# Humus_ethernet_dip_v2.net
KiCad netlist of a schematic drawn in EAGLE
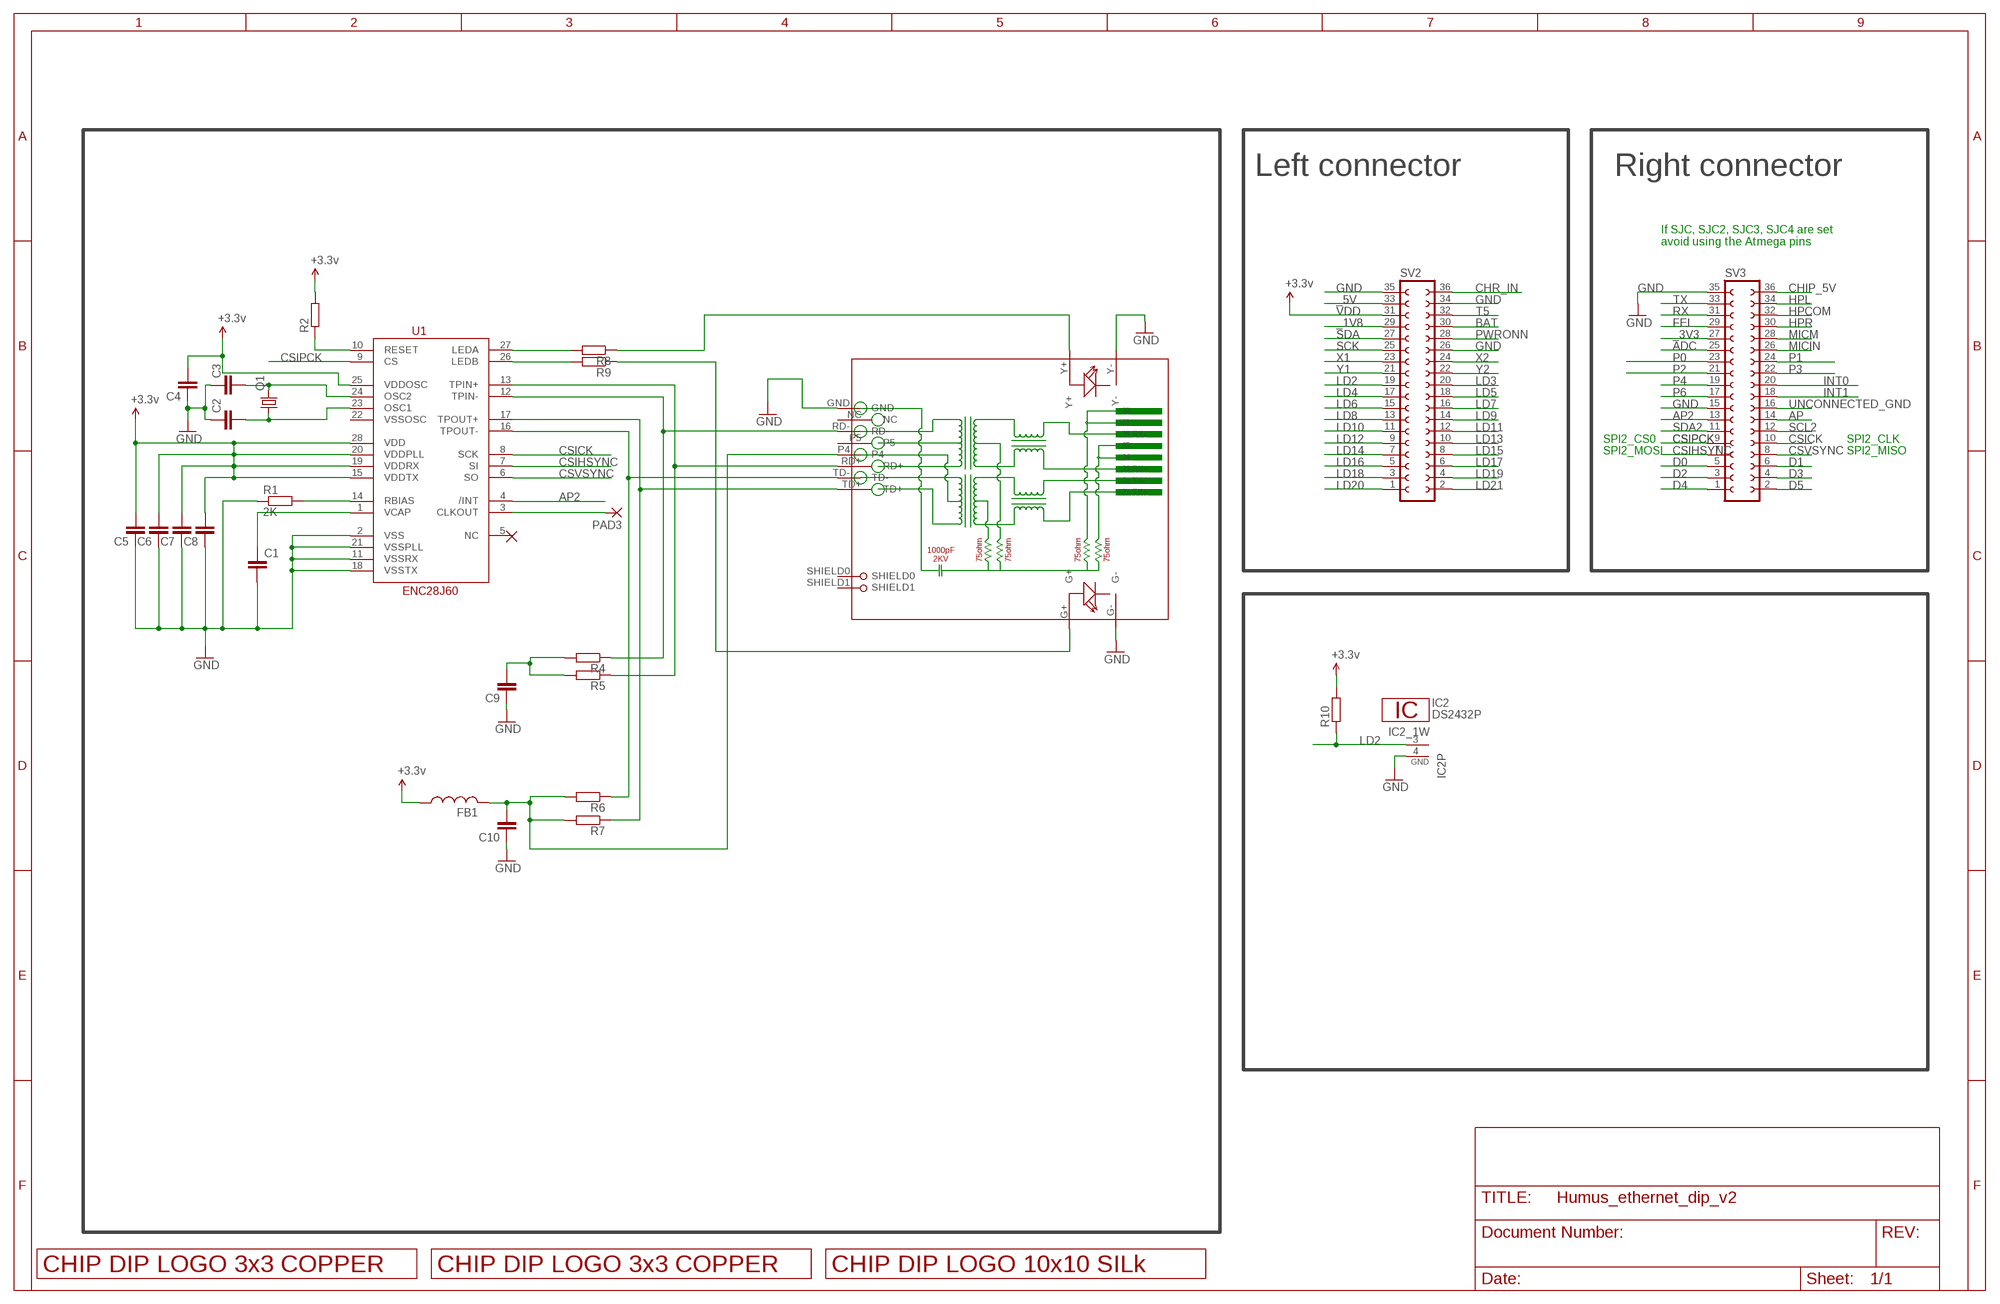
[diagram p0: schematic, sheet 1]

(export (version "E")
  (design (tool "Eeschema 10.0.6"))
  (components
    (comp (ref "C1")
      (value "C-EUC0805")
      (footprint "eagle-import:C0805")
      (libsource (lib "eagle-import") (part "C-EUC0805"))
    )
    (comp (ref "C2")
      (value "C-EUC0805")
      (footprint "eagle-import:C0805")
      (libsource (lib "eagle-import") (part "C-EUC0805"))
    )
    (comp (ref "C3")
      (value "C-EUC0805")
      (footprint "eagle-import:C0805")
      (libsource (lib "eagle-import") (part "C-EUC0805"))
    )
    (comp (ref "C4")
      (value "C-EUC0805")
      (footprint "eagle-import:C0805")
      (libsource (lib "eagle-import") (part "C-EUC0805"))
    )
    (comp (ref "C5")
      (value "C-EUC0805")
      (footprint "eagle-import:C0805")
      (libsource (lib "eagle-import") (part "C-EUC0805"))
    )
    (comp (ref "C6")
      (value "C-EUC0805")
      (footprint "eagle-import:C0805")
      (libsource (lib "eagle-import") (part "C-EUC0805"))
    )
    (comp (ref "C7")
      (value "C-EUC0805")
      (footprint "eagle-import:C0805")
      (libsource (lib "eagle-import") (part "C-EUC0805"))
    )
    (comp (ref "C8")
      (value "C-EUC0805")
      (footprint "eagle-import:C0805")
      (libsource (lib "eagle-import") (part "C-EUC0805"))
    )
    (comp (ref "C9")
      (value "C-EUC0805")
      (footprint "eagle-import:C0805")
      (libsource (lib "eagle-import") (part "C-EUC0805"))
    )
    (comp (ref "C10")
      (value "C-EUC0805")
      (footprint "eagle-import:C0805")
      (libsource (lib "eagle-import") (part "C-EUC0805"))
    )
    (comp (ref "FB1")
      (value "FERRITE-BEADB")
      (footprint "eagle-import:0805")
      (libsource (lib "eagle-import") (part "FERRITE-BEADB"))
    )
    (comp (ref "IC2")
      (value "DS2432P")
      (footprint "eagle-import:TSOC6")
      (libsource (lib "eagle-import") (part "DS2432P"))
    )
    (comp (ref "PAD3")
      (value "WIREPADSMD1,27-254")
      (footprint "eagle-import:SMD1,27-2,54")
      (libsource (lib "eagle-import") (part "WIREPADSMD1,27-254"))
    )
    (comp (ref "Q1")
      (value "CRYSTALSM49")
      (footprint "eagle-import:SM49")
      (libsource (lib "eagle-import") (part "CRYSTALSM49"))
    )
    (comp (ref "R1")
      (value "2K")
      (footprint "eagle-import:R0805")
      (libsource (lib "eagle-import") (part "R-EU_R0805"))
    )
    (comp (ref "R2")
      (value "R-EU_R0805")
      (footprint "eagle-import:R0805")
      (libsource (lib "eagle-import") (part "R-EU_R0805"))
    )
    (comp (ref "R4")
      (value "R-EU_R0805")
      (footprint "eagle-import:R0805")
      (libsource (lib "eagle-import") (part "R-EU_R0805"))
    )
    (comp (ref "R5")
      (value "R-EU_R0805")
      (footprint "eagle-import:R0805")
      (libsource (lib "eagle-import") (part "R-EU_R0805"))
    )
    (comp (ref "R6")
      (value "R-EU_R0805")
      (footprint "eagle-import:R0805")
      (libsource (lib "eagle-import") (part "R-EU_R0805"))
    )
    (comp (ref "R7")
      (value "R-EU_R0805")
      (footprint "eagle-import:R0805")
      (libsource (lib "eagle-import") (part "R-EU_R0805"))
    )
    (comp (ref "R8")
      (value "R-EU_R0805")
      (footprint "eagle-import:R0805")
      (libsource (lib "eagle-import") (part "R-EU_R0805"))
    )
    (comp (ref "R9")
      (value "R-EU_R0805")
      (footprint "eagle-import:R0805")
      (libsource (lib "eagle-import") (part "R-EU_R0805"))
    )
    (comp (ref "R10")
      (value "R-EU_R0805")
      (footprint "eagle-import:R0805")
      (libsource (lib "eagle-import") (part "R-EU_R0805"))
    )
    (comp (ref "RJ1")
      (value "HR911105A")
      (footprint "eagle-import:HR911105A")
      (libsource (lib "eagle-import") (part "HR911105A"))
    )
    (comp (ref "SV2")
      (value "FE18-2")
      (footprint "eagle-import:FE18-2")
      (libsource (lib "eagle-import") (part "FE18-2"))
    )
    (comp (ref "SV3")
      (value "FE18-2")
      (footprint "eagle-import:FE18-2")
      (libsource (lib "eagle-import") (part "FE18-2"))
    )
    (comp (ref "U$2")
      (value "LOGO_3X3_COPPER")
      (footprint "eagle-import:LOGO_3X3_COPPER")
      (libsource (lib "eagle-import") (part "LOGO_3X3_COPPER"))
    )
    (comp (ref "U$4")
      (value "LOGO_3X3_COPPER")
      (footprint "eagle-import:LOGO_3X3_COPPER")
      (libsource (lib "eagle-import") (part "LOGO_3X3_COPPER"))
    )
    (comp (ref "U$5")
      (value "LOGO_10X10_SILK")
      (footprint "eagle-import:LOGO_10X10_SILK")
      (libsource (lib "eagle-import") (part "LOGO_10X10_SILK"))
    )
    (comp (ref "U1")
      (value "ENC28J60")
      (footprint "eagle-import:SSOP28DB")
      (libsource (lib "eagle-import") (part "ENC28J60"))
    )
  )
  (nets
    (net (code "1") (name "+3.3v") (class "Default")
      (node (ref "C4") (pin "2") (pinfunction "2_2") (pintype "passive"))
      (node (ref "C5") (pin "2") (pinfunction "2_2") (pintype "passive"))
      (node (ref "C6") (pin "2") (pinfunction "2_2") (pintype "passive"))
      (node (ref "C7") (pin "2") (pinfunction "2_2") (pintype "passive"))
      (node (ref "C8") (pin "2") (pinfunction "2_2") (pintype "passive"))
      (node (ref "FB1") (pin "1") (pinfunction "1_1") (pintype "passive"))
      (node (ref "R10") (pin "2") (pinfunction "2_2") (pintype "passive"))
      (node (ref "R2") (pin "2") (pinfunction "2_2") (pintype "passive"))
      (node (ref "SV2") (pin "31") (pinfunction "31_31") (pintype "passive"))
      (node (ref "U1") (pin "15") (pinfunction "VDDTX_15") (pintype "bidirectional"))
      (node (ref "U1") (pin "19") (pinfunction "VDDRX_19") (pintype "bidirectional"))
      (node (ref "U1") (pin "20") (pinfunction "VDDPLL_20") (pintype "bidirectional"))
      (node (ref "U1") (pin "25") (pinfunction "VDDOSC_25") (pintype "bidirectional"))
      (node (ref "U1") (pin "28") (pinfunction "VDD_28") (pintype "bidirectional"))
    )
    (net (code "2") (name "/ADC") (class "Default")
      (node (ref "SV3") (pin "25") (pinfunction "25_25") (pintype "passive"))
    )
    (net (code "3") (name "/AP") (class "Default")
      (node (ref "SV3") (pin "14") (pinfunction "14_14") (pintype "passive"))
    )
    (net (code "4") (name "/AP2") (class "Default")
      (node (ref "SV3") (pin "13") (pinfunction "13_13") (pintype "passive"))
      (node (ref "U1") (pin "4") (pinfunction "/INT_4") (pintype "bidirectional"))
    )
    (net (code "5") (name "/BAT") (class "Default")
      (node (ref "SV2") (pin "30") (pinfunction "30_30") (pintype "passive"))
    )
    (net (code "6") (name "/CHIP_5V") (class "Default")
      (node (ref "SV3") (pin "36") (pinfunction "36_36") (pintype "passive"))
    )
    (net (code "7") (name "/CHR_IN") (class "Default")
      (node (ref "SV2") (pin "36") (pinfunction "36_36") (pintype "passive"))
    )
    (net (code "8") (name "/CSICK") (class "Default")
      (node (ref "SV3") (pin "10") (pinfunction "10_10") (pintype "passive"))
      (node (ref "U1") (pin "8") (pinfunction "SCK_8") (pintype "bidirectional"))
    )
    (net (code "9") (name "/CSIHSYNC") (class "Default")
      (node (ref "SV3") (pin "7") (pinfunction "7_7") (pintype "passive"))
      (node (ref "U1") (pin "7") (pinfunction "SI_7") (pintype "bidirectional"))
    )
    (net (code "10") (name "/CSIPCK") (class "Default")
      (node (ref "SV3") (pin "9") (pinfunction "9_9") (pintype "passive"))
      (node (ref "U1") (pin "9") (pinfunction "CS_9") (pintype "bidirectional"))
    )
    (net (code "11") (name "/CSVSYNC") (class "Default")
      (node (ref "SV3") (pin "8") (pinfunction "8_8") (pintype "passive"))
      (node (ref "U1") (pin "6") (pinfunction "SO_6") (pintype "bidirectional"))
    )
    (net (code "12") (name "/D0") (class "Default")
      (node (ref "SV3") (pin "5") (pinfunction "5_5") (pintype "passive"))
    )
    (net (code "13") (name "/D1") (class "Default")
      (node (ref "SV3") (pin "6") (pinfunction "6_6") (pintype "passive"))
    )
    (net (code "14") (name "/D2") (class "Default")
      (node (ref "SV3") (pin "3") (pinfunction "3_3") (pintype "passive"))
    )
    (net (code "15") (name "/D3") (class "Default")
      (node (ref "SV3") (pin "4") (pinfunction "4_4") (pintype "passive"))
    )
    (net (code "16") (name "/D4") (class "Default")
      (node (ref "SV3") (pin "1") (pinfunction "1_1") (pintype "passive"))
    )
    (net (code "17") (name "/D5") (class "Default")
      (node (ref "SV3") (pin "2") (pinfunction "2_2") (pintype "passive"))
    )
    (net (code "18") (name "/FEL") (class "Default")
      (node (ref "SV3") (pin "29") (pinfunction "29_29") (pintype "passive"))
    )
    (net (code "19") (name "/HPCOM") (class "Default")
      (node (ref "SV3") (pin "32") (pinfunction "32_32") (pintype "passive"))
    )
    (net (code "20") (name "/HPL") (class "Default")
      (node (ref "SV3") (pin "34") (pinfunction "34_34") (pintype "passive"))
    )
    (net (code "21") (name "/HPR") (class "Default")
      (node (ref "SV3") (pin "30") (pinfunction "30_30") (pintype "passive"))
    )
    (net (code "22") (name "/INT0") (class "Default")
      (node (ref "SV3") (pin "20") (pinfunction "20_20") (pintype "passive"))
    )
    (net (code "23") (name "/INT1") (class "Default")
      (node (ref "SV3") (pin "18") (pinfunction "18_18") (pintype "passive"))
    )
    (net (code "24") (name "/LD2") (class "Default")
      (node (ref "IC2") (pin "3") (pinfunction "1W_3") (pintype "power_in"))
      (node (ref "R10") (pin "1") (pinfunction "1_1") (pintype "passive"))
      (node (ref "SV2") (pin "19") (pinfunction "19_19") (pintype "passive"))
    )
    (net (code "25") (name "/LD3") (class "Default")
      (node (ref "SV2") (pin "20") (pinfunction "20_20") (pintype "passive"))
    )
    (net (code "26") (name "/LD4") (class "Default")
      (node (ref "SV2") (pin "17") (pinfunction "17_17") (pintype "passive"))
    )
    (net (code "27") (name "/LD5") (class "Default")
      (node (ref "SV2") (pin "18") (pinfunction "18_18") (pintype "passive"))
    )
    (net (code "28") (name "/LD6") (class "Default")
      (node (ref "SV2") (pin "15") (pinfunction "15_15") (pintype "passive"))
    )
    (net (code "29") (name "/LD7") (class "Default")
      (node (ref "SV2") (pin "16") (pinfunction "16_16") (pintype "passive"))
    )
    (net (code "30") (name "/LD8") (class "Default")
      (node (ref "SV2") (pin "13") (pinfunction "13_13") (pintype "passive"))
    )
    (net (code "31") (name "/LD9") (class "Default")
      (node (ref "SV2") (pin "14") (pinfunction "14_14") (pintype "passive"))
    )
    (net (code "32") (name "/LD10") (class "Default")
      (node (ref "SV2") (pin "11") (pinfunction "11_11") (pintype "passive"))
    )
    (net (code "33") (name "/LD11") (class "Default")
      (node (ref "SV2") (pin "12") (pinfunction "12_12") (pintype "passive"))
    )
    (net (code "34") (name "/LD12") (class "Default")
      (node (ref "SV2") (pin "9") (pinfunction "9_9") (pintype "passive"))
    )
    (net (code "35") (name "/LD13") (class "Default")
      (node (ref "SV2") (pin "10") (pinfunction "10_10") (pintype "passive"))
    )
    (net (code "36") (name "/LD14") (class "Default")
      (node (ref "SV2") (pin "7") (pinfunction "7_7") (pintype "passive"))
    )
    (net (code "37") (name "/LD15") (class "Default")
      (node (ref "SV2") (pin "8") (pinfunction "8_8") (pintype "passive"))
    )
    (net (code "38") (name "/LD16") (class "Default")
      (node (ref "SV2") (pin "5") (pinfunction "5_5") (pintype "passive"))
    )
    (net (code "39") (name "/LD17") (class "Default")
      (node (ref "SV2") (pin "6") (pinfunction "6_6") (pintype "passive"))
    )
    (net (code "40") (name "/LD18") (class "Default")
      (node (ref "SV2") (pin "3") (pinfunction "3_3") (pintype "passive"))
    )
    (net (code "41") (name "/LD19") (class "Default")
      (node (ref "SV2") (pin "4") (pinfunction "4_4") (pintype "passive"))
    )
    (net (code "42") (name "/LD20") (class "Default")
      (node (ref "SV2") (pin "1") (pinfunction "1_1") (pintype "passive"))
    )
    (net (code "43") (name "/LD21") (class "Default")
      (node (ref "SV2") (pin "2") (pinfunction "2_2") (pintype "passive"))
    )
    (net (code "44") (name "/MICIN") (class "Default")
      (node (ref "SV3") (pin "26") (pinfunction "26_26") (pintype "passive"))
    )
    (net (code "45") (name "/MICM") (class "Default")
      (node (ref "SV3") (pin "28") (pinfunction "28_28") (pintype "passive"))
    )
    (net (code "46") (name "/P0") (class "Default")
      (node (ref "SV3") (pin "23") (pinfunction "23_23") (pintype "passive"))
    )
    (net (code "47") (name "/P1") (class "Default")
      (node (ref "SV3") (pin "24") (pinfunction "24_24") (pintype "passive"))
    )
    (net (code "48") (name "/P2") (class "Default")
      (node (ref "SV3") (pin "21") (pinfunction "21_21") (pintype "passive"))
    )
    (net (code "49") (name "/P3") (class "Default")
      (node (ref "SV3") (pin "22") (pinfunction "22_22") (pintype "passive"))
    )
    (net (code "50") (name "/P4") (class "Default")
      (node (ref "SV3") (pin "19") (pinfunction "19_19") (pintype "passive"))
    )
    (net (code "51") (name "/P6") (class "Default")
      (node (ref "SV3") (pin "17") (pinfunction "17_17") (pintype "passive"))
    )
    (net (code "52") (name "/PWRONN") (class "Default")
      (node (ref "SV2") (pin "28") (pinfunction "28_28") (pintype "passive"))
    )
    (net (code "53") (name "/RX") (class "Default")
      (node (ref "SV3") (pin "31") (pinfunction "31_31") (pintype "passive"))
    )
    (net (code "54") (name "/SCK") (class "Default")
      (node (ref "SV2") (pin "25") (pinfunction "25_25") (pintype "passive"))
    )
    (net (code "55") (name "/SCL2") (class "Default")
      (node (ref "SV3") (pin "12") (pinfunction "12_12") (pintype "passive"))
    )
    (net (code "56") (name "/SDA") (class "Default")
      (node (ref "SV2") (pin "27") (pinfunction "27_27") (pintype "passive"))
    )
    (net (code "57") (name "/SDA2") (class "Default")
      (node (ref "SV3") (pin "11") (pinfunction "11_11") (pintype "passive"))
    )
    (net (code "58") (name "/T5") (class "Default")
      (node (ref "SV2") (pin "32") (pinfunction "32_32") (pintype "passive"))
    )
    (net (code "59") (name "/TX") (class "Default")
      (node (ref "SV3") (pin "33") (pinfunction "33_33") (pintype "passive"))
    )
    (net (code "60") (name "/UNCONNECTED_GND") (class "Default")
      (node (ref "SV3") (pin "16") (pinfunction "16_16") (pintype "passive"))
    )
    (net (code "61") (name "/X1") (class "Default")
      (node (ref "SV2") (pin "23") (pinfunction "23_23") (pintype "passive"))
    )
    (net (code "62") (name "/X2") (class "Default")
      (node (ref "SV2") (pin "24") (pinfunction "24_24") (pintype "passive"))
    )
    (net (code "63") (name "/Y1") (class "Default")
      (node (ref "SV2") (pin "21") (pinfunction "21_21") (pintype "passive"))
    )
    (net (code "64") (name "/Y2") (class "Default")
      (node (ref "SV2") (pin "22") (pinfunction "22_22") (pintype "passive"))
    )
    (net (code "65") (name "/_1V8") (class "Default")
      (node (ref "SV2") (pin "29") (pinfunction "29_29") (pintype "passive"))
    )
    (net (code "66") (name "/_3V3") (class "Default")
      (node (ref "SV3") (pin "27") (pinfunction "27_27") (pintype "passive"))
    )
    (net (code "67") (name "/_5V") (class "Default")
      (node (ref "SV2") (pin "33") (pinfunction "33_33") (pintype "passive"))
    )
    (net (code "68") (name "GND") (class "Default")
      (node (ref "C1") (pin "2") (pinfunction "2_2") (pintype "passive"))
      (node (ref "C10") (pin "1") (pinfunction "1_1") (pintype "passive"))
      (node (ref "C2") (pin "1") (pinfunction "1_1") (pintype "passive"))
      (node (ref "C3") (pin "1") (pinfunction "1_1") (pintype "passive"))
      (node (ref "C4") (pin "1") (pinfunction "1_1") (pintype "passive"))
      (node (ref "C5") (pin "1") (pinfunction "1_1") (pintype "passive"))
      (node (ref "C6") (pin "1") (pinfunction "1_1") (pintype "passive"))
      (node (ref "C7") (pin "1") (pinfunction "1_1") (pintype "passive"))
      (node (ref "C8") (pin "1") (pinfunction "1_1") (pintype "passive"))
      (node (ref "C9") (pin "1") (pinfunction "1_1") (pintype "passive"))
      (node (ref "IC2") (pin "4") (pinfunction "GND_4") (pintype "power_in"))
      (node (ref "R1") (pin "1") (pinfunction "1_1") (pintype "passive"))
      (node (ref "RJ1") (pin "G-") (pinfunction "G-_G-") (pintype "bidirectional"))
      (node (ref "RJ1") (pin "GND") (pinfunction "GND_GND") (pintype "bidirectional"))
      (node (ref "RJ1") (pin "Y-") (pinfunction "Y-_Y-") (pintype "bidirectional"))
      (node (ref "SV2") (pin "26") (pinfunction "26_26") (pintype "passive"))
      (node (ref "SV2") (pin "34") (pinfunction "34_34") (pintype "passive"))
      (node (ref "SV2") (pin "35") (pinfunction "35_35") (pintype "passive"))
      (node (ref "SV3") (pin "15") (pinfunction "15_15") (pintype "passive"))
      (node (ref "SV3") (pin "35") (pinfunction "35_35") (pintype "passive"))
      (node (ref "U1") (pin "11") (pinfunction "VSSRX_11") (pintype "bidirectional"))
      (node (ref "U1") (pin "18") (pinfunction "VSSTX_18") (pintype "bidirectional"))
      (node (ref "U1") (pin "2") (pinfunction "VSS_2") (pintype "bidirectional"))
      (node (ref "U1") (pin "21") (pinfunction "VSSPLL_21") (pintype "bidirectional"))
    )
    (net (code "69") (name "Net-(C9-Pad2)") (class "Default")
      (node (ref "C9") (pin "2") (pinfunction "2_2") (pintype "passive"))
      (node (ref "R4") (pin "2") (pinfunction "2_2") (pintype "passive"))
      (node (ref "R5") (pin "2") (pinfunction "2_2") (pintype "passive"))
    )
    (net (code "70") (name "Net-(C10-Pad2)") (class "Default")
      (node (ref "C10") (pin "2") (pinfunction "2_2") (pintype "passive"))
      (node (ref "FB1") (pin "2") (pinfunction "2_2") (pintype "passive"))
      (node (ref "R6") (pin "2") (pinfunction "2_2") (pintype "passive"))
      (node (ref "R7") (pin "2") (pinfunction "2_2") (pintype "passive"))
      (node (ref "RJ1") (pin "P4") (pinfunction "P4_P4") (pintype "bidirectional"))
    )
    (net (code "71") (name "Net-(PAD3-P)") (class "Default")
      (node (ref "PAD3") (pin "1") (pinfunction "P_1") (pintype "passive"))
      (node (ref "U1") (pin "3") (pinfunction "CLKOUT_3") (pintype "bidirectional"))
    )
    (net (code "72") (name "Net-(R8-Pad1)") (class "Default")
      (node (ref "R8") (pin "1") (pinfunction "1_1") (pintype "passive"))
      (node (ref "RJ1") (pin "Y+") (pinfunction "Y+_Y+") (pintype "bidirectional"))
    )
    (net (code "73") (name "Net-(R9-Pad1)") (class "Default")
      (node (ref "R9") (pin "1") (pinfunction "1_1") (pintype "passive"))
      (node (ref "RJ1") (pin "G+") (pinfunction "G+_G+") (pintype "bidirectional"))
    )
    (net (code "74") (name "Net-(U1-LEDA)") (class "Default")
      (node (ref "R8") (pin "2") (pinfunction "2_2") (pintype "passive"))
      (node (ref "U1") (pin "27") (pinfunction "LEDA_27") (pintype "bidirectional"))
    )
    (net (code "75") (name "Net-(U1-LEDB)") (class "Default")
      (node (ref "R9") (pin "2") (pinfunction "2_2") (pintype "passive"))
      (node (ref "U1") (pin "26") (pinfunction "LEDB_26") (pintype "bidirectional"))
    )
    (net (code "76") (name "Net-(U1-OSC1)") (class "Default")
      (node (ref "C2") (pin "2") (pinfunction "2_2") (pintype "passive"))
      (node (ref "Q1") (pin "1") (pinfunction "1_1") (pintype "passive"))
      (node (ref "U1") (pin "23") (pinfunction "OSC1_23") (pintype "bidirectional"))
    )
    (net (code "77") (name "Net-(U1-OSC2)") (class "Default")
      (node (ref "C3") (pin "2") (pinfunction "2_2") (pintype "passive"))
      (node (ref "Q1") (pin "2") (pinfunction "2_2") (pintype "passive"))
      (node (ref "U1") (pin "24") (pinfunction "OSC2_24") (pintype "bidirectional"))
    )
    (net (code "78") (name "Net-(U1-RBIAS)") (class "Default")
      (node (ref "R1") (pin "2") (pinfunction "2_2") (pintype "passive"))
      (node (ref "U1") (pin "14") (pinfunction "RBIAS_14") (pintype "bidirectional"))
    )
    (net (code "79") (name "Net-(U1-RESET)") (class "Default")
      (node (ref "R2") (pin "1") (pinfunction "1_1") (pintype "passive"))
      (node (ref "U1") (pin "10") (pinfunction "RESET_10") (pintype "bidirectional"))
    )
    (net (code "80") (name "Net-(U1-TPIN+)") (class "Default")
      (node (ref "R5") (pin "1") (pinfunction "1_1") (pintype "passive"))
      (node (ref "RJ1") (pin "RD+") (pinfunction "RD+_RD+") (pintype "bidirectional"))
      (node (ref "U1") (pin "13") (pinfunction "TPIN+_13") (pintype "bidirectional"))
    )
    (net (code "81") (name "Net-(U1-TPIN-)") (class "Default")
      (node (ref "R4") (pin "1") (pinfunction "1_1") (pintype "passive"))
      (node (ref "RJ1") (pin "RD-") (pinfunction "RD-_RD-") (pintype "bidirectional"))
      (node (ref "U1") (pin "12") (pinfunction "TPIN-_12") (pintype "bidirectional"))
    )
    (net (code "82") (name "Net-(U1-TPOUT+)") (class "Default")
      (node (ref "R7") (pin "1") (pinfunction "1_1") (pintype "passive"))
      (node (ref "RJ1") (pin "TD+") (pinfunction "TD+_TD+") (pintype "bidirectional"))
      (node (ref "U1") (pin "17") (pinfunction "TPOUT+_17") (pintype "bidirectional"))
    )
    (net (code "83") (name "Net-(U1-TPOUT-)") (class "Default")
      (node (ref "R6") (pin "1") (pinfunction "1_1") (pintype "passive"))
      (node (ref "RJ1") (pin "TD-") (pinfunction "TD-_TD-") (pintype "bidirectional"))
      (node (ref "U1") (pin "16") (pinfunction "TPOUT-_16") (pintype "bidirectional"))
    )
    (net (code "84") (name "Net-(U1-VCAP)") (class "Default")
      (node (ref "C1") (pin "1") (pinfunction "1_1") (pintype "passive"))
      (node (ref "U1") (pin "1") (pinfunction "VCAP_1") (pintype "bidirectional"))
    )
    (net (code "85") (name "unconnected-(RJ1-PadNC)") (class "Default")
      (node (ref "RJ1") (pin "NC") (pinfunction "NC_NC") (pintype "bidirectional"))
    )
    (net (code "86") (name "unconnected-(RJ1-PadP5)") (class "Default")
      (node (ref "RJ1") (pin "P5") (pinfunction "P5_P5") (pintype "bidirectional"))
    )
    (net (code "87") (name "unconnected-(RJ1-PadSHIELD0)") (class "Default")
      (node (ref "RJ1") (pin "SHIELD0") (pinfunction "SHIELD0_SHIELD0") (pintype "bidirectional"))
    )
    (net (code "88") (name "unconnected-(RJ1-PadSHIELD1)") (class "Default")
      (node (ref "RJ1") (pin "SHIELD1") (pinfunction "SHIELD1_SHIELD1") (pintype "bidirectional"))
    )
    (net (code "89") (name "unconnected-(U1-NC-Pad5)") (class "Default")
      (node (ref "U1") (pin "5") (pinfunction "NC_5") (pintype "bidirectional"))
    )
    (net (code "90") (name "unconnected-(U1-VSSOSC-Pad22)") (class "Default")
      (node (ref "U1") (pin "22") (pinfunction "VSSOSC_22") (pintype "bidirectional"))
    )
  )
)
